# A1.net
KiCad netlist of a schematic drawn in Altium Designer
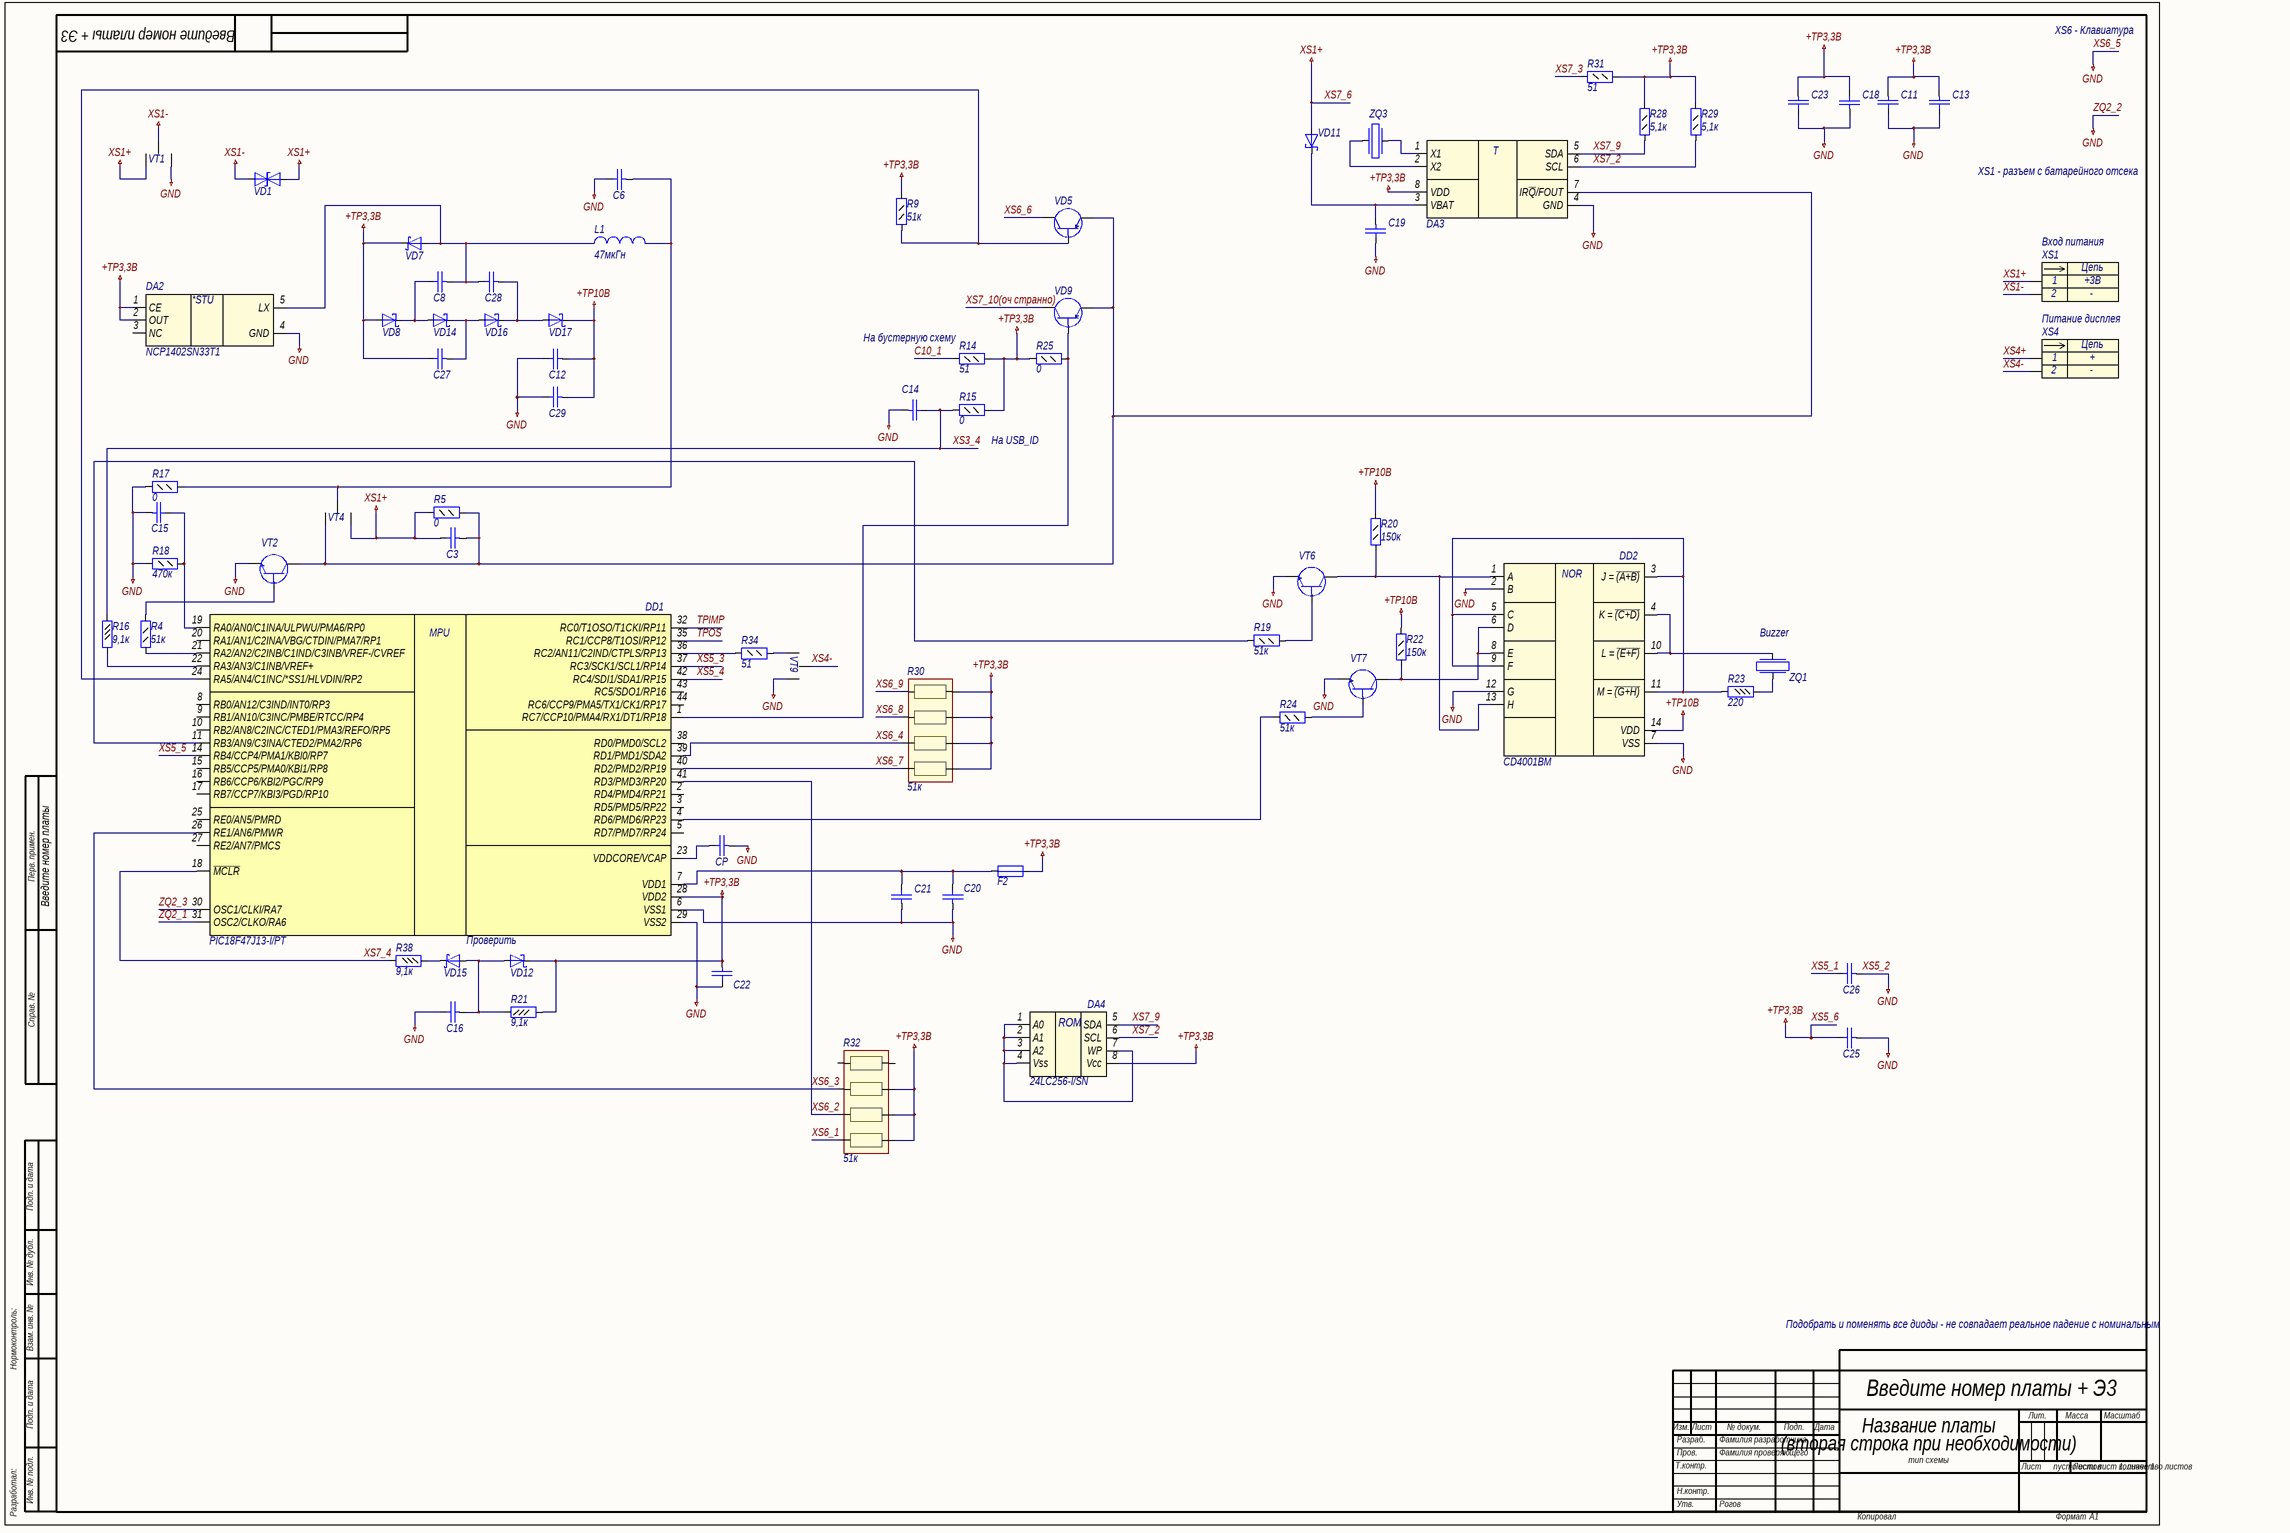
[diagram p0: A1.SchDoc]

(export (version "E")
  (design (tool "Eeschema 10.0.6"))
  (components
    (comp (ref "C3")
      (value "Capacitor")
      (footprint "C0402")
      (description "Конденсатор")
      (fields (field (name "VOLTAGE") "50B") (field (name "PART NUMBER") "GRP1555C1HR47CZ01E"))
      (libsource (lib "MOP44") (part "Capacitor"))
    )
    (comp (ref "C6")
      (value "Capacitor")
      (footprint "C0402")
      (description "Конденсатор")
      (fields (field (name "VOLTAGE") "50B") (field (name "PART NUMBER") "GRP1555C1HR47CZ01E"))
      (libsource (lib "MOP44") (part "Capacitor"))
    )
    (comp (ref "C8")
      (value "Capacitor")
      (footprint "C0402")
      (description "Конденсатор")
      (fields (field (name "VOLTAGE") "50B") (field (name "PART NUMBER") "GRP1555C1HR47CZ01E"))
      (libsource (lib "MOP44") (part "Capacitor"))
    )
    (comp (ref "C11")
      (value "Capacitor")
      (footprint "C0402")
      (description "Конденсатор")
      (fields (field (name "VOLTAGE") "50B") (field (name "PART NUMBER") "GRP1555C1HR47CZ01E"))
      (libsource (lib "MOP44") (part "Capacitor"))
    )
    (comp (ref "C12")
      (value "Capacitor")
      (footprint "C0402")
      (description "Конденсатор")
      (fields (field (name "VOLTAGE") "50B") (field (name "PART NUMBER") "GRP1555C1HR47CZ01E"))
      (libsource (lib "MOP44") (part "Capacitor"))
    )
    (comp (ref "C13")
      (value "Capacitor")
      (footprint "C0402")
      (description "Конденсатор")
      (fields (field (name "VOLTAGE") "50B") (field (name "PART NUMBER") "GRP1555C1HR47CZ01E"))
      (libsource (lib "MOP44") (part "Capacitor"))
    )
    (comp (ref "C14")
      (value "Capacitor")
      (footprint "C0402")
      (description "Конденсатор")
      (fields (field (name "VOLTAGE") "50B") (field (name "PART NUMBER") "GRP1555C1HR47CZ01E"))
      (libsource (lib "MOP44") (part "Capacitor"))
    )
    (comp (ref "C15")
      (value "Capacitor")
      (footprint "C0402")
      (description "Конденсатор")
      (fields (field (name "VOLTAGE") "50B") (field (name "PART NUMBER") "GRP1555C1HR47CZ01E"))
      (libsource (lib "MOP44") (part "Capacitor"))
    )
    (comp (ref "C16")
      (value "Capacitor")
      (footprint "C0402")
      (description "Конденсатор")
      (fields (field (name "VOLTAGE") "50B") (field (name "PART NUMBER") "GRP1555C1HR47CZ01E"))
      (libsource (lib "MOP44") (part "Capacitor"))
    )
    (comp (ref "C18")
      (value "Capacitor")
      (footprint "C0402")
      (description "Конденсатор")
      (fields (field (name "VOLTAGE") "50B") (field (name "PART NUMBER") "GRP1555C1HR47CZ01E"))
      (libsource (lib "MOP44") (part "Capacitor"))
    )
    (comp (ref "C19")
      (value "Capacitor")
      (footprint "C0402")
      (description "Конденсатор")
      (fields (field (name "VOLTAGE") "50B") (field (name "PART NUMBER") "GRP1555C1HR47CZ01E"))
      (libsource (lib "MOP44") (part "Capacitor"))
    )
    (comp (ref "C20")
      (value "Capacitor")
      (footprint "C0402")
      (description "Конденсатор")
      (fields (field (name "VOLTAGE") "50B") (field (name "PART NUMBER") "GRP1555C1HR47CZ01E"))
      (libsource (lib "MOP44") (part "Capacitor"))
    )
    (comp (ref "C21")
      (value "Capacitor")
      (footprint "C0402")
      (description "Конденсатор")
      (fields (field (name "VOLTAGE") "50B") (field (name "PART NUMBER") "GRP1555C1HR47CZ01E"))
      (libsource (lib "MOP44") (part "Capacitor"))
    )
    (comp (ref "C22")
      (value "Capacitor")
      (footprint "C0402")
      (description "Конденсатор")
      (fields (field (name "VOLTAGE") "50B") (field (name "PART NUMBER") "GRP1555C1HR47CZ01E"))
      (libsource (lib "MOP44") (part "Capacitor"))
    )
    (comp (ref "C23")
      (value "Capacitor")
      (footprint "C0402")
      (description "Конденсатор")
      (fields (field (name "VOLTAGE") "50B") (field (name "PART NUMBER") "GRP1555C1HR47CZ01E"))
      (libsource (lib "MOP44") (part "Capacitor"))
    )
    (comp (ref "C25")
      (value "Capacitor")
      (footprint "C0402")
      (description "Конденсатор")
      (fields (field (name "VOLTAGE") "50B") (field (name "PART NUMBER") "GRP1555C1HR47CZ01E"))
      (libsource (lib "MOP44") (part "Capacitor"))
    )
    (comp (ref "C26")
      (value "Capacitor")
      (footprint "C0402")
      (description "Конденсатор")
      (fields (field (name "VOLTAGE") "50B") (field (name "PART NUMBER") "GRP1555C1HR47CZ01E"))
      (libsource (lib "MOP44") (part "Capacitor"))
    )
    (comp (ref "C27")
      (value "Capacitor")
      (footprint "C0402")
      (description "Конденсатор")
      (fields (field (name "VOLTAGE") "50B") (field (name "PART NUMBER") "GRP1555C1HR47CZ01E"))
      (libsource (lib "MOP44") (part "Capacitor"))
    )
    (comp (ref "C28")
      (value "Capacitor")
      (footprint "C0402")
      (description "Конденсатор")
      (fields (field (name "VOLTAGE") "50B") (field (name "PART NUMBER") "GRP1555C1HR47CZ01E"))
      (libsource (lib "MOP44") (part "Capacitor"))
    )
    (comp (ref "C29")
      (value "Capacitor")
      (footprint "C0402")
      (description "Конденсатор")
      (fields (field (name "VOLTAGE") "50B") (field (name "PART NUMBER") "GRP1555C1HR47CZ01E"))
      (libsource (lib "MOP44") (part "Capacitor"))
    )
    (comp (ref "CP")
      (value "Capacitor")
      (footprint "C0402")
      (description "Конденсатор")
      (fields (field (name "VOLTAGE") "50B") (field (name "PART NUMBER") "GRP1555C1HR47CZ01E"))
      (libsource (lib "MOP44") (part "Capacitor"))
    )
    (comp (ref "DA2")
      (value "NCP1402")
      (footprint "SOT23-5")
      (description "Step-up DC-DC Converter for 2-V to 3.3-V")
      (fields (field (name "PART NUMBER") "NCP1402SN33T1") (field (name "MANUFACTURER") "ON Semiconductor"))
      (libsource (lib "MOP44") (part "NCP1402"))
    )
    (comp (ref "DA3")
      (value "ISL1208IB8Z")
      (footprint "SO8")
      (description "Часы реального времени/календарь")
      (libsource (lib "MOP44") (part "ISL1208IB8Z"))
    )
    (comp (ref "DA4")
      (value "24LC256-I/SN")
      (footprint "SO8")
      (description "Последовательная энергонезависимая память 32x8kbit")
      (fields (field (name "PART NUMBER") "24LC256-I/SN") (field (name "MANUFACTURER") "Microchip"))
      (libsource (lib "MOP44") (part "24LC256-I/SN"))
    )
    (comp (ref "DD1")
      (value "PIC18F47J13-I/PT")
      (footprint "TQFP-44")
      (description "Микроконтроллер 8-Бит, 44-pin")
      (libsource (lib "MOP44") (part "PIC18F47J13-I/PT"))
    )
    (comp (ref "DD2")
      (value "CD4001BM")
      (footprint "SO14")
      (description "CMOS NOR Gate 4-Element 2-IN")
      (libsource (lib "MOP44") (part "CD4001BM"))
    )
    (comp (ref "F2")
      (value "Fuse")
      (footprint "FUSE812")
      (description "Предохранитель")
      (fields (field (name "PART NUMBER") "MF-MSMF075"))
      (libsource (lib "MOP44") (part "Fuse"))
    )
    (comp (ref "L1")
      (value "47мкГн")
      (footprint "SDR0604")
      (description "EMI Suppression Filter")
      (fields (field (name "PART NUMBER") "SDR0604- 470KL") (field (name "Comment") "Inductor"))
      (libsource (lib "MOP44") (part "Inductor"))
    )
    (comp (ref "R4")
      (value "51к")
      (footprint "R0805")
      (description "Резистор")
      (fields (field (name "PART NUMBER") "RC0805FR-0751KL") (field (name "POWER") "0,125Вт"))
      (libsource (lib "MOP44") (part "Resistor_0,125Вт"))
    )
    (comp (ref "R5")
      (value "0")
      (footprint "R0805")
      (description "Резистор")
      (fields (field (name "PART NUMBER") "RC0805FR-070RL") (field (name "POWER") "0,125Вт"))
      (libsource (lib "") (part "Resistor_0,125Вт_1"))
    )
    (comp (ref "R9")
      (value "51к")
      (footprint "R0805")
      (description "Резистор")
      (fields (field (name "PART NUMBER") "RC0805FR-0751KL") (field (name "POWER") "0,125Вт"))
      (libsource (lib "MOP44") (part "Resistor_0,125Вт"))
    )
    (comp (ref "R14")
      (value "51")
      (footprint "R0805")
      (description "Резистор")
      (fields (field (name "PART NUMBER") "RC0805FR-0751RL") (field (name "POWER") "0,125Вт"))
      (libsource (lib "") (part "Resistor_0,125Вт_1"))
    )
    (comp (ref "R15")
      (value "0")
      (footprint "R0805")
      (description "Резистор")
      (fields (field (name "PART NUMBER") "RC0805FR-070RL") (field (name "POWER") "0,125Вт"))
      (libsource (lib "") (part "Resistor_0,125Вт_1"))
    )
    (comp (ref "R16")
      (value "9,1к")
      (footprint "R0603")
      (description "Резистор")
      (fields (field (name "PART NUMBER") "RC0603FR-079K1") (field (name "POWER") "0,062Вт"))
      (libsource (lib "") (part "Resistor_0,062Вт_2"))
    )
    (comp (ref "R17")
      (value "0")
      (footprint "R0805")
      (description "Резистор")
      (fields (field (name "PART NUMBER") "RC0805FR-070RL") (field (name "POWER") "0,125Вт"))
      (libsource (lib "") (part "Resistor_0,125Вт_1"))
    )
    (comp (ref "R18")
      (value "470к")
      (footprint "R0805")
      (description "Резистор")
      (fields (field (name "PART NUMBER") "RC0805FR-07470KL") (field (name "POWER") "0,125Вт"))
      (libsource (lib "") (part "Resistor_0,125Вт_2"))
    )
    (comp (ref "R19")
      (value "51к")
      (footprint "R0805")
      (description "Резистор")
      (fields (field (name "PART NUMBER") "RC0805FR-0751KL") (field (name "POWER") "0,125Вт"))
      (libsource (lib "") (part "Resistor_0,125Вт_1"))
    )
    (comp (ref "R20")
      (value "150к")
      (footprint "R0805")
      (description "Резистор")
      (fields (field (name "PART NUMBER") "RC0805FR-07150KL") (field (name "POWER") "0,125Вт"))
      (libsource (lib "MOP44") (part "Resistor_0,125Вт"))
    )
    (comp (ref "R21")
      (value "9,1к")
      (footprint "R0603")
      (description "Резистор")
      (fields (field (name "PART NUMBER") "RC0603FR-079K1") (field (name "POWER") "0,062Вт"))
      (libsource (lib "") (part "Resistor_0,062Вт_1"))
    )
    (comp (ref "R22")
      (value "150к")
      (footprint "R0805")
      (description "Резистор")
      (fields (field (name "PART NUMBER") "RC0805FR-07150KL") (field (name "POWER") "0,125Вт"))
      (libsource (lib "MOP44") (part "Resistor_0,125Вт"))
    )
    (comp (ref "R23")
      (value "220")
      (footprint "R0603")
      (description "Резистор")
      (fields (field (name "PART NUMBER") "RC0603FR-07220RL") (field (name "POWER") "0,062Вт"))
      (libsource (lib "MOP44") (part "Resistor_0,062Вт"))
    )
    (comp (ref "R24")
      (value "51к")
      (footprint "R0805")
      (description "Резистор")
      (fields (field (name "PART NUMBER") "RC0805FR-0751KL") (field (name "POWER") "0,125Вт"))
      (libsource (lib "") (part "Resistor_0,125Вт_1"))
    )
    (comp (ref "R25")
      (value "0")
      (footprint "R0805")
      (description "Резистор")
      (fields (field (name "PART NUMBER") "RC0805FR-070RL") (field (name "POWER") "0,125Вт"))
      (libsource (lib "") (part "Resistor_0,125Вт_1"))
    )
    (comp (ref "R28")
      (value "5,1к")
      (footprint "R0805")
      (description "Резистор")
      (fields (field (name "PART NUMBER") "RC0805FR-075K1") (field (name "POWER") "0,125Вт"))
      (libsource (lib "MOP44") (part "Resistor_0,125Вт"))
    )
    (comp (ref "R29")
      (value "5,1к")
      (footprint "R0805")
      (description "Резистор")
      (fields (field (name "PART NUMBER") "RC0805FR-075K1") (field (name "POWER") "0,125Вт"))
      (libsource (lib "MOP44") (part "Resistor_0,125Вт"))
    )
    (comp (ref "R30")
      (value "51к")
      (footprint "4xR1206")
      (description "Резисторная сборка")
      (fields (field (name "PART NUMBER") "TC164-JR-0751KL") (field (name "POWER") "0,062Вт"))
      (libsource (lib "MOP44") (part "Resistors_array_4x0,062Вт"))
    )
    (comp (ref "R31")
      (value "51")
      (footprint "R0805")
      (description "Резистор")
      (fields (field (name "PART NUMBER") "RC0805FR-0751RL") (field (name "POWER") "0,125Вт"))
      (libsource (lib "") (part "Resistor_0,125Вт_2"))
    )
    (comp (ref "R32")
      (value "51к")
      (footprint "4xR1206")
      (description "Резисторная сборка")
      (fields (field (name "PART NUMBER") "TC164-JR-0751KL") (field (name "POWER") "0,062Вт"))
      (libsource (lib "MOP44") (part "Resistors_array_4x0,062Вт"))
    )
    (comp (ref "R34")
      (value "51")
      (footprint "R0805")
      (description "Резистор")
      (fields (field (name "PART NUMBER") "RC0805FR-0751RL") (field (name "POWER") "0,125Вт"))
      (libsource (lib "") (part "Resistor_0,125Вт_2"))
    )
    (comp (ref "R38")
      (value "9,1к")
      (footprint "R0603")
      (description "Резистор")
      (fields (field (name "PART NUMBER") "RC0603FR-079K1") (field (name "POWER") "0,062Вт"))
      (libsource (lib "MOP44") (part "Resistor_0,062Вт"))
    )
    (comp (ref "VD1")
      (value "DiodeZenerDual")
      (footprint "SMB")
      (description "Cтабилитрон (диод выпрямительный лавинный) двусторонний")
      (fields (field (name "PART NUMBER") "SMBJ8.5CA"))
      (libsource (lib "MOP44") (part "DiodeZenerDual"))
    )
    (comp (ref "VD5")
      (value "BJT PNP")
      (footprint "SOT23-3")
      (fields (field (name "POWER") "0,31Вт") (field (name "PART NUMBER") "BC807-40"))
      (libsource (lib "MOP44") (part "BJT PNP"))
    )
    (comp (ref "VD7")
      (value "DiodeSchottky")
      (footprint "SOD-123")
      (description "Диод Шоттки")
      (fields (field (name "PART NUMBER") "MBR0520LT1"))
      (libsource (lib "MOP44") (part "DiodeSchottky"))
    )
    (comp (ref "VD8")
      (value "DiodeSchottky")
      (footprint "SOD-123")
      (description "Диод Шоттки")
      (fields (field (name "PART NUMBER") "MBR0520LT1"))
      (libsource (lib "MOP44") (part "DiodeSchottky"))
    )
    (comp (ref "VD9")
      (value "BJT PNP")
      (footprint "SOT23-3")
      (fields (field (name "POWER") "0,31Вт") (field (name "PART NUMBER") "BC807-40"))
      (libsource (lib "MOP44") (part "BJT PNP"))
    )
    (comp (ref "VD11")
      (value "DiodeSchottky")
      (footprint "SOD-123")
      (description "Диод Шоттки")
      (fields (field (name "PART NUMBER") "MBR0540"))
      (libsource (lib "MOP44") (part "DiodeSchottky"))
    )
    (comp (ref "VD12")
      (value "DiodeSchottky")
      (footprint "SOD-123")
      (description "Диод Шоттки")
      (fields (field (name "PART NUMBER") "MBR0520LT1"))
      (libsource (lib "MOP44") (part "DiodeSchottky"))
    )
    (comp (ref "VD14")
      (value "DiodeSchottky")
      (footprint "SOD-123")
      (description "Диод Шоттки")
      (fields (field (name "PART NUMBER") "MBR0520LT1"))
      (libsource (lib "MOP44") (part "DiodeSchottky"))
    )
    (comp (ref "VD15")
      (value "DiodeSchottky")
      (footprint "SOD-123")
      (description "Диод Шоттки")
      (fields (field (name "PART NUMBER") "MBR0520LT1"))
      (libsource (lib "MOP44") (part "DiodeSchottky"))
    )
    (comp (ref "VD16")
      (value "DiodeSchottky")
      (footprint "SOD-123")
      (description "Диод Шоттки")
      (fields (field (name "PART NUMBER") "MBR0520LT1"))
      (libsource (lib "MOP44") (part "DiodeSchottky"))
    )
    (comp (ref "VD17")
      (value "DiodeSchottky")
      (footprint "SOD-123")
      (description "Диод Шоттки")
      (fields (field (name "PART NUMBER") "MBR0520LT1"))
      (libsource (lib "MOP44") (part "DiodeSchottky"))
    )
    (comp (ref "VT2")
      (value "BJT NPN")
      (footprint "SOT23-3")
      (fields (field (name "POWER") "0,25Bт") (field (name "PART NUMBER") "BC847C"))
      (libsource (lib "MOP44") (part "BJT NPN"))
    )
    (comp (ref "VT6")
      (value "BJT NPN")
      (footprint "SOT23-3")
      (fields (field (name "POWER") "0,25Bт") (field (name "PART NUMBER") "BC847C"))
      (libsource (lib "MOP44") (part "BJT NPN"))
    )
    (comp (ref "VT7")
      (value "BJT NPN")
      (footprint "SOT23-3")
      (fields (field (name "POWER") "0,25Bт") (field (name "PART NUMBER") "BC847C"))
      (libsource (lib "MOP44") (part "BJT NPN"))
    )
    (comp (ref "XS1")
      (value "Вход питания")
      (footprint "CWF-2")
      (description "Разъем - 2 конт. вилка")
      (fields (field (name "PART NUMBER") "DS1069-2MVW6X"))
      (libsource (lib "MOP44") (part "Header_2_plg"))
    )
    (comp (ref "XS4")
      (value "Питание дисплея")
      (footprint "CWF-2")
      (description "Разъем - 2 конт. вилка")
      (fields (field (name "PART NUMBER") "DS1069-2MVW6X"))
      (libsource (lib "MOP44") (part "Header_2_plg"))
    )
    (comp (ref "ZQ1")
      (value "~")
      (footprint "Buzzer_9mm")
      (description "Пьезоизлучатель звуковой без генератора")
      (fields (field (name "PART NUMBER") "HC0905F"))
      (libsource (lib "MOP44") (part "Buzzer"))
    )
    (comp (ref "ZQ3")
      (value "Crystal")
      (footprint "QSMD7x1.5x1.4")
      (description "Кварцевый резонатор")
      (fields (field (name "PART NUMBER") "KX-327LT"))
      (libsource (lib "MOP44") (part "Crystal"))
    )
  )
  (nets
    (net (code "1") (name "+TP3,3В") (class "Default")
      (node (ref "C11") (pin "1") (pinfunction "1_1") (pintype "passive"))
      (node (ref "C13") (pin "1") (pinfunction "1_1") (pintype "passive"))
      (node (ref "C18") (pin "2") (pinfunction "2_2") (pintype "passive"))
      (node (ref "C22") (pin "1") (pinfunction "1_1") (pintype "passive"))
      (node (ref "C23") (pin "1") (pinfunction "1_1") (pintype "passive"))
      (node (ref "C25") (pin "2") (pinfunction "2_2") (pintype "passive"))
      (node (ref "C27") (pin "2") (pinfunction "2_2") (pintype "passive"))
      (node (ref "DA2") (pin "1") (pinfunction "CE_1") (pintype "power_in"))
      (node (ref "DA2") (pin "2") (pinfunction "OUT_2") (pintype "power_in"))
      (node (ref "DA3") (pin "8") (pinfunction "VDD_8") (pintype "power_in"))
      (node (ref "DA4") (pin "8") (pinfunction "Vcc_8") (pintype "passive"))
      (node (ref "DD1") (pin "28") (pinfunction "VDD2_28") (pintype "passive"))
      (node (ref "F2") (pin "2") (pinfunction "2_2") (pintype "passive"))
      (node (ref "R14") (pin "2") (pinfunction "2_2") (pintype "passive"))
      (node (ref "R15") (pin "2") (pinfunction "2_2") (pintype "passive"))
      (node (ref "R21") (pin "2") (pinfunction "2_2") (pintype "passive"))
      (node (ref "R25") (pin "1") (pinfunction "1_1") (pintype "passive"))
      (node (ref "R28") (pin "2") (pinfunction "2_2") (pintype "passive"))
      (node (ref "R29") (pin "2") (pinfunction "2_2") (pintype "passive"))
      (node (ref "R30") (pin "2") (pinfunction "2_2") (pintype "passive"))
      (node (ref "R30") (pin "4") (pinfunction "4_4") (pintype "passive"))
      (node (ref "R30") (pin "6") (pinfunction "6_6") (pintype "passive"))
      (node (ref "R30") (pin "8") (pinfunction "8_8") (pintype "passive"))
      (node (ref "R31") (pin "1") (pinfunction "1_1") (pintype "passive"))
      (node (ref "R32") (pin "4") (pinfunction "4_4") (pintype "passive"))
      (node (ref "R32") (pin "6") (pinfunction "6_6") (pintype "passive"))
      (node (ref "R32") (pin "8") (pinfunction "8_8") (pintype "passive"))
      (node (ref "R9") (pin "2") (pinfunction "2_2") (pintype "passive"))
      (node (ref "VD12") (pin "1") (pinfunction "K_1") (pintype "passive"))
      (node (ref "VD7") (pin "1") (pinfunction "K_1") (pintype "passive"))
      (node (ref "VD8") (pin "2") (pinfunction "A_2") (pintype "passive"))
    )
    (net (code "2") (name "+TP10В") (class "Default")
      (node (ref "C12") (pin "1") (pinfunction "1_1") (pintype "passive"))
      (node (ref "C29") (pin "1") (pinfunction "1_1") (pintype "passive"))
      (node (ref "DD2") (pin "14") (pinfunction "VDD_14") (pintype "power_in"))
      (node (ref "R20") (pin "2") (pinfunction "2_2") (pintype "passive"))
      (node (ref "R22") (pin "2") (pinfunction "2_2") (pintype "passive"))
      (node (ref "VD17") (pin "1") (pinfunction "K_1") (pintype "passive"))
    )
    (net (code "3") (name "/C10_1") (class "Default")
      (node (ref "R14") (pin "1") (pinfunction "1_1") (pintype "passive"))
    )
    (net (code "4") (name "/TPIMP") (class "Default")
      (node (ref "DD1") (pin "32") (pinfunction "RC0/T1OSO/T1CKI/RP11_32") (pintype "passive"))
    )
    (net (code "5") (name "/TPOS") (class "Default")
      (node (ref "DD1") (pin "35") (pinfunction "RC1/CCP8/T1OSI/RP12_35") (pintype "passive"))
    )
    (net (code "6") (name "/XS3_4") (class "Default")
      (node (ref "C14") (pin "2") (pinfunction "2_2") (pintype "passive"))
      (node (ref "R15") (pin "1") (pinfunction "1_1") (pintype "passive"))
      (node (ref "R16") (pin "1") (pinfunction "1_1") (pintype "passive"))
    )
    (net (code "7") (name "/XS4+") (class "Default")
      (node (ref "XS4") (pin "1") (pinfunction "1_1") (pintype "passive"))
    )
    (net (code "8") (name "/XS4-") (class "Default")
      (node (ref "XS4") (pin "2") (pinfunction "2_2") (pintype "passive"))
    )
    (net (code "9") (name "/XS5_1") (class "Default")
      (node (ref "C26") (pin "2") (pinfunction "2_2") (pintype "passive"))
    )
    (net (code "10") (name "/XS5_3") (class "Default")
      (node (ref "DD1") (pin "37") (pinfunction "RC3/SCK1/SCL1/RP14_37") (pintype "passive"))
    )
    (net (code "11") (name "/XS5_4") (class "Default")
      (node (ref "DD1") (pin "42") (pinfunction "RC4/SDI1/SDA1/RP15_42") (pintype "passive"))
    )
    (net (code "12") (name "/XS5_5") (class "Default")
      (node (ref "DD1") (pin "14") (pinfunction "RB4/CCP4/PMA1/KBI0/RP7_14") (pintype "passive"))
    )
    (net (code "13") (name "/XS6_1") (class "Default")
      (node (ref "R32") (pin "7") (pinfunction "7_7") (pintype "passive"))
    )
    (net (code "14") (name "/XS6_2") (class "Default")
      (node (ref "DD1") (pin "26") (pinfunction "RE1/AN6/PMWR_26") (pintype "passive"))
      (node (ref "DD1") (pin "41") (pinfunction "RD3/PMD3/RP20_41") (pintype "passive"))
      (node (ref "R32") (pin "3") (pinfunction "3_3") (pintype "passive"))
      (node (ref "R32") (pin "5") (pinfunction "5_5") (pintype "passive"))
    )
    (net (code "15") (name "/XS6_4") (class "Default")
      (node (ref "DD1") (pin "39") (pinfunction "RD1/PMD1/SDA2_39") (pintype "passive"))
      (node (ref "R30") (pin "5") (pinfunction "5_5") (pintype "passive"))
    )
    (net (code "16") (name "/XS6_6") (class "Default")
      (node (ref "VD5") (pin "3") (pinfunction "3_3") (pintype "passive"))
    )
    (net (code "17") (name "/XS6_7") (class "Default")
      (node (ref "DD1") (pin "40") (pinfunction "RD2/PMD2/RP19_40") (pintype "passive"))
      (node (ref "R30") (pin "7") (pinfunction "7_7") (pintype "passive"))
    )
    (net (code "18") (name "/XS6_8") (class "Default")
      (node (ref "R30") (pin "3") (pinfunction "3_3") (pintype "passive"))
    )
    (net (code "19") (name "/XS6_9") (class "Default")
      (node (ref "R30") (pin "1") (pinfunction "1_1") (pintype "passive"))
    )
    (net (code "20") (name "/XS7_2") (class "Default")
      (node (ref "DA3") (pin "6") (pinfunction "SCL_6") (pintype "power_in"))
      (node (ref "DA4") (pin "6") (pinfunction "SCL_6") (pintype "passive"))
      (node (ref "R29") (pin "1") (pinfunction "1_1") (pintype "passive"))
    )
    (net (code "21") (name "/XS7_3") (class "Default")
      (node (ref "R31") (pin "2") (pinfunction "2_2") (pintype "passive"))
    )
    (net (code "22") (name "/XS7_4") (class "Default")
      (node (ref "DD1") (pin "18") (pinfunction "~{MCLR}_18") (pintype "passive"))
      (node (ref "R38") (pin "2") (pinfunction "2_2") (pintype "passive"))
    )
    (net (code "23") (name "/XS7_9") (class "Default")
      (node (ref "DA3") (pin "5") (pinfunction "SDA_5") (pintype "power_in"))
      (node (ref "DA4") (pin "5") (pinfunction "SDA_5") (pintype "passive"))
      (node (ref "R28") (pin "1") (pinfunction "1_1") (pintype "passive"))
    )
    (net (code "24") (name "/XS7_10(оч странно)") (class "Default")
      (node (ref "VD9") (pin "3") (pinfunction "3_3") (pintype "passive"))
    )
    (net (code "25") (name "/ZQ2_1") (class "Default")
      (node (ref "DD1") (pin "31") (pinfunction "OSC2/CLKO/RA6_31") (pintype "passive"))
    )
    (net (code "26") (name "/ZQ2_3") (class "Default")
      (node (ref "DD1") (pin "30") (pinfunction "OSC1/CLKI/RA7_30") (pintype "passive"))
    )
    (net (code "27") (name "GND") (class "Default")
      (node (ref "C11") (pin "2") (pinfunction "2_2") (pintype "passive"))
      (node (ref "C12") (pin "2") (pinfunction "2_2") (pintype "passive"))
      (node (ref "C13") (pin "2") (pinfunction "2_2") (pintype "passive"))
      (node (ref "C14") (pin "1") (pinfunction "1_1") (pintype "passive"))
      (node (ref "C15") (pin "1") (pinfunction "1_1") (pintype "passive"))
      (node (ref "C16") (pin "2") (pinfunction "2_2") (pintype "passive"))
      (node (ref "C18") (pin "1") (pinfunction "1_1") (pintype "passive"))
      (node (ref "C19") (pin "2") (pinfunction "2_2") (pintype "passive"))
      (node (ref "C20") (pin "1") (pinfunction "1_1") (pintype "passive"))
      (node (ref "C21") (pin "1") (pinfunction "1_1") (pintype "passive"))
      (node (ref "C22") (pin "2") (pinfunction "2_2") (pintype "passive"))
      (node (ref "C23") (pin "2") (pinfunction "2_2") (pintype "passive"))
      (node (ref "C25") (pin "1") (pinfunction "1_1") (pintype "passive"))
      (node (ref "C26") (pin "1") (pinfunction "1_1") (pintype "passive"))
      (node (ref "C29") (pin "2") (pinfunction "2_2") (pintype "passive"))
      (node (ref "C6") (pin "2") (pinfunction "2_2") (pintype "passive"))
      (node (ref "CP") (pin "1") (pinfunction "1_1") (pintype "passive"))
      (node (ref "DA2") (pin "4") (pinfunction "GND_4") (pintype "power_in"))
      (node (ref "DA3") (pin "4") (pinfunction "GND_4") (pintype "power_in"))
      (node (ref "DD1") (pin "29") (pinfunction "VSS2_29") (pintype "passive"))
      (node (ref "DD1") (pin "6") (pinfunction "VSS1_6") (pintype "passive"))
      (node (ref "DD2") (pin "12") (pinfunction "G_12") (pintype "passive"))
      (node (ref "DD2") (pin "2") (pinfunction "B_2") (pintype "passive"))
      (node (ref "DD2") (pin "7") (pinfunction "VSS_7") (pintype "power_in"))
      (node (ref "R17") (pin "1") (pinfunction "1_1") (pintype "passive"))
      (node (ref "R18") (pin "2") (pinfunction "2_2") (pintype "passive"))
      (node (ref "VT2") (pin "2") (pinfunction "2_2") (pintype "passive"))
      (node (ref "VT6") (pin "2") (pinfunction "2_2") (pintype "passive"))
      (node (ref "VT7") (pin "2") (pinfunction "2_2") (pintype "passive"))
    )
    (net (code "28") (name "Net-(C6-Pad1)") (class "Default")
      (node (ref "C6") (pin "1") (pinfunction "1_1") (pintype "passive"))
      (node (ref "L1") (pin "2") (pinfunction "2_2") (pintype "passive"))
      (node (ref "R17") (pin "2") (pinfunction "2_2") (pintype "passive"))
    )
    (net (code "29") (name "Net-(DA2-LX)") (class "Default")
      (node (ref "C28") (pin "2") (pinfunction "2_2") (pintype "passive"))
      (node (ref "C8") (pin "1") (pinfunction "1_1") (pintype "passive"))
      (node (ref "DA2") (pin "5") (pinfunction "LX_5") (pintype "power_in"))
      (node (ref "L1") (pin "1") (pinfunction "1_1") (pintype "passive"))
      (node (ref "VD7") (pin "2") (pinfunction "A_2") (pintype "passive"))
    )
    (net (code "30") (name "Net-(DA3-IR~{Q}{slash}FOUT)") (class "Default")
      (node (ref "C3") (pin "1") (pinfunction "1_1") (pintype "passive"))
      (node (ref "DA3") (pin "7") (pinfunction "IR~{Q}/FOUT_7") (pintype "power_in"))
      (node (ref "R5") (pin "2") (pinfunction "2_2") (pintype "passive"))
      (node (ref "VD5") (pin "2") (pinfunction "2_2") (pintype "passive"))
      (node (ref "VD9") (pin "2") (pinfunction "2_2") (pintype "passive"))
      (node (ref "VT2") (pin "3") (pinfunction "3_3") (pintype "passive"))
    )
    (net (code "31") (name "Net-(DA3-VBAT)") (class "Default")
      (node (ref "C19") (pin "1") (pinfunction "1_1") (pintype "passive"))
      (node (ref "DA3") (pin "3") (pinfunction "VBAT_3") (pintype "power_in"))
      (node (ref "VD11") (pin "1") (pinfunction "K_1") (pintype "passive"))
    )
    (net (code "32") (name "Net-(DA3-X1)") (class "Default")
      (node (ref "DA3") (pin "1") (pinfunction "X1_1") (pintype "power_in"))
      (node (ref "ZQ3") (pin "2") (pinfunction "2_2") (pintype "passive"))
    )
    (net (code "33") (name "Net-(DA3-X2)") (class "Default")
      (node (ref "DA3") (pin "2") (pinfunction "X2_2") (pintype "power_in"))
      (node (ref "ZQ3") (pin "1") (pinfunction "1_1") (pintype "passive"))
    )
    (net (code "34") (name "Net-(DA4-A0)") (class "Default")
      (node (ref "DA4") (pin "1") (pinfunction "A0_1") (pintype "passive"))
      (node (ref "DA4") (pin "2") (pinfunction "A1_2") (pintype "passive"))
      (node (ref "DA4") (pin "3") (pinfunction "A2_3") (pintype "passive"))
      (node (ref "DA4") (pin "4") (pinfunction "Vss_4") (pintype "passive"))
      (node (ref "DA4") (pin "7") (pinfunction "WP_7") (pintype "passive"))
    )
    (net (code "35") (name "Net-(DD1-RA0{slash}AN0{slash}C1INA{slash}ULPWU{slash}PMA6{slash}RP0)") (class "Default")
      (node (ref "C15") (pin "2") (pinfunction "2_2") (pintype "passive"))
      (node (ref "DD1") (pin "19") (pinfunction "RA0/AN0/C1INA/ULPWU/PMA6/RP0_19") (pintype "passive"))
      (node (ref "R18") (pin "1") (pinfunction "1_1") (pintype "passive"))
    )
    (net (code "36") (name "Net-(DD1-RA2{slash}AN2{slash}C2INB{slash}C1IND{slash}C3INB{slash}VREF-{slash}CVREF)") (class "Default")
      (node (ref "DD1") (pin "21") (pinfunction "RA2/AN2/C2INB/C1IND/C3INB/VREF-/CVREF_21") (pintype "passive"))
      (node (ref "R4") (pin "1") (pinfunction "1_1") (pintype "passive"))
    )
    (net (code "37") (name "Net-(DD1-RA3{slash}AN3{slash}C1INB{slash}VREF+)") (class "Default")
      (node (ref "DD1") (pin "22") (pinfunction "RA3/AN3/C1INB/VREF+_22") (pintype "passive"))
      (node (ref "R16") (pin "2") (pinfunction "2_2") (pintype "passive"))
    )
    (net (code "38") (name "Net-(DD1-RA5{slash}AN4{slash}C1INC{slash}*SS1{slash}HLVDIN{slash}RP2)") (class "Default")
      (node (ref "DD1") (pin "24") (pinfunction "RA5/AN4/C1INC/*SS1/HLVDIN/RP2_24") (pintype "passive"))
      (node (ref "R9") (pin "1") (pinfunction "1_1") (pintype "passive"))
      (node (ref "VD5") (pin "1") (pinfunction "1_1") (pintype "passive"))
    )
    (net (code "39") (name "Net-(DD1-RB3{slash}AN9{slash}C3INA{slash}CTED2{slash}PMA2{slash}RP6)") (class "Default")
      (node (ref "DD1") (pin "11") (pinfunction "RB3/AN9/C3INA/CTED2/PMA2/RP6_11") (pintype "passive"))
      (node (ref "R19") (pin "1") (pinfunction "1_1") (pintype "passive"))
    )
    (net (code "40") (name "Net-(DD1-RC2{slash}AN11{slash}C2IND{slash}CTPLS{slash}RP13)") (class "Default")
      (node (ref "DD1") (pin "36") (pinfunction "RC2/AN11/C2IND/CTPLS/RP13_36") (pintype "passive"))
      (node (ref "R34") (pin "2") (pinfunction "2_2") (pintype "passive"))
    )
    (net (code "41") (name "Net-(DD1-RC7{slash}CCP10{slash}PMA4{slash}RX1{slash}DT1{slash}RP18)") (class "Default")
      (node (ref "DD1") (pin "1") (pinfunction "RC7/CCP10/PMA4/RX1/DT1/RP18_1") (pintype "passive"))
      (node (ref "R25") (pin "2") (pinfunction "2_2") (pintype "passive"))
      (node (ref "VD9") (pin "1") (pinfunction "1_1") (pintype "passive"))
    )
    (net (code "42") (name "Net-(DD1-RD6{slash}PMD6{slash}RP23)") (class "Default")
      (node (ref "DD1") (pin "4") (pinfunction "RD6/PMD6/RP23_4") (pintype "passive"))
      (node (ref "R24") (pin "1") (pinfunction "1_1") (pintype "passive"))
    )
    (net (code "43") (name "Net-(DD1-VDD1)") (class "Default")
      (node (ref "C20") (pin "2") (pinfunction "2_2") (pintype "passive"))
      (node (ref "C21") (pin "2") (pinfunction "2_2") (pintype "passive"))
      (node (ref "DD1") (pin "7") (pinfunction "VDD1_7") (pintype "passive"))
      (node (ref "F2") (pin "1") (pinfunction "1_1") (pintype "passive"))
    )
    (net (code "44") (name "Net-(DD1-VDDCORE{slash}VCAP)") (class "Default")
      (node (ref "CP") (pin "2") (pinfunction "2_2") (pintype "passive"))
      (node (ref "DD1") (pin "23") (pinfunction "VDDCORE/VCAP_23") (pintype "passive"))
    )
    (net (code "45") (name "Net-(DD2-A)") (class "Default")
      (node (ref "DD2") (pin "1") (pinfunction "A_1") (pintype "passive"))
      (node (ref "DD2") (pin "13") (pinfunction "H_13") (pintype "passive"))
      (node (ref "R20") (pin "1") (pinfunction "1_1") (pintype "passive"))
      (node (ref "VT6") (pin "3") (pinfunction "3_3") (pintype "passive"))
    )
    (net (code "46") (name "Net-(DD2-C)") (class "Default")
      (node (ref "DD2") (pin "11") (pinfunction "M_=_~{(G+H)}_11") (pintype "passive"))
      (node (ref "DD2") (pin "3") (pinfunction "J_=_~{(A+B)}_3") (pintype "passive"))
      (node (ref "DD2") (pin "5") (pinfunction "C_5") (pintype "passive"))
      (node (ref "DD2") (pin "9") (pinfunction "F_9") (pintype "passive"))
      (node (ref "R23") (pin "2") (pinfunction "2_2") (pintype "passive"))
    )
    (net (code "47") (name "Net-(DD2-D)") (class "Default")
      (node (ref "DD2") (pin "6") (pinfunction "D_6") (pintype "passive"))
      (node (ref "DD2") (pin "8") (pinfunction "E_8") (pintype "passive"))
      (node (ref "R22") (pin "1") (pinfunction "1_1") (pintype "passive"))
      (node (ref "VT7") (pin "3") (pinfunction "3_3") (pintype "passive"))
    )
    (net (code "48") (name "Net-(DD2-K_=_~{(C+D)})") (class "Default")
      (node (ref "DD2") (pin "10") (pinfunction "L_=_~{(E+F)}_10") (pintype "passive"))
      (node (ref "DD2") (pin "4") (pinfunction "K_=_~{(C+D)}_4") (pintype "passive"))
      (node (ref "ZQ1") (pin "2") (pinfunction "2_2") (pintype "passive"))
    )
    (net (code "49") (name "Net-(R4-Pad2)") (class "Default")
      (node (ref "R4") (pin "2") (pinfunction "2_2") (pintype "passive"))
      (node (ref "VT2") (pin "1") (pinfunction "1_1") (pintype "passive"))
    )
    (net (code "50") (name "Net-(R19-Pad2)") (class "Default")
      (node (ref "R19") (pin "2") (pinfunction "2_2") (pintype "passive"))
      (node (ref "VT6") (pin "1") (pinfunction "1_1") (pintype "passive"))
    )
    (net (code "51") (name "Net-(R23-Pad1)") (class "Default")
      (node (ref "R23") (pin "1") (pinfunction "1_1") (pintype "passive"))
      (node (ref "ZQ1") (pin "1") (pinfunction "1_1") (pintype "passive"))
    )
    (net (code "52") (name "Net-(R24-Pad2)") (class "Default")
      (node (ref "R24") (pin "2") (pinfunction "2_2") (pintype "passive"))
      (node (ref "VT7") (pin "1") (pinfunction "1_1") (pintype "passive"))
    )
    (net (code "53") (name "Net-(VD12-A)") (class "Default")
      (node (ref "C16") (pin "1") (pinfunction "1_1") (pintype "passive"))
      (node (ref "R21") (pin "1") (pinfunction "1_1") (pintype "passive"))
      (node (ref "VD12") (pin "2") (pinfunction "A_2") (pintype "passive"))
      (node (ref "VD15") (pin "2") (pinfunction "A_2") (pintype "passive"))
    )
    (net (code "54") (name "Net-(VD14-A)") (class "Default")
      (node (ref "C8") (pin "2") (pinfunction "2_2") (pintype "passive"))
      (node (ref "VD14") (pin "2") (pinfunction "A_2") (pintype "passive"))
      (node (ref "VD8") (pin "1") (pinfunction "K_1") (pintype "passive"))
    )
    (net (code "55") (name "Net-(VD14-K)") (class "Default")
      (node (ref "C27") (pin "1") (pinfunction "1_1") (pintype "passive"))
      (node (ref "VD14") (pin "1") (pinfunction "K_1") (pintype "passive"))
      (node (ref "VD16") (pin "2") (pinfunction "A_2") (pintype "passive"))
    )
    (net (code "56") (name "Net-(VD15-K)") (class "Default")
      (node (ref "R38") (pin "1") (pinfunction "1_1") (pintype "passive"))
      (node (ref "VD15") (pin "1") (pinfunction "K_1") (pintype "passive"))
    )
    (net (code "57") (name "Net-(VD16-K)") (class "Default")
      (node (ref "C28") (pin "1") (pinfunction "1_1") (pintype "passive"))
      (node (ref "VD16") (pin "1") (pinfunction "K_1") (pintype "passive"))
      (node (ref "VD17") (pin "2") (pinfunction "A_2") (pintype "passive"))
    )
    (net (code "58") (name "XS1+") (class "Default")
      (node (ref "C3") (pin "2") (pinfunction "2_2") (pintype "passive"))
      (node (ref "R5") (pin "1") (pinfunction "1_1") (pintype "passive"))
      (node (ref "VD1") (pin "1") (pinfunction "K_1") (pintype "passive"))
      (node (ref "VD11") (pin "2") (pinfunction "A_2") (pintype "passive"))
      (node (ref "XS1") (pin "1") (pinfunction "1_1") (pintype "passive"))
    )
    (net (code "59") (name "XS1-") (class "Default")
      (node (ref "VD1") (pin "2") (pinfunction "A_2") (pintype "passive"))
      (node (ref "XS1") (pin "2") (pinfunction "2_2") (pintype "passive"))
    )
    (net (code "60") (name "unconnected-(DA2-NC-Pad3)") (class "Default")
      (node (ref "DA2") (pin "3") (pinfunction "NC_3") (pintype "power_in"))
    )
    (net (code "61") (name "unconnected-(DD1-RA1{slash}AN1{slash}C2INA{slash}VBG{slash}CTDIN{slash}PMA7{slash}RP1-Pad20)") (class "Default")
      (node (ref "DD1") (pin "20") (pinfunction "RA1/AN1/C2INA/VBG/CTDIN/PMA7/RP1_20") (pintype "passive"))
    )
    (net (code "62") (name "unconnected-(DD1-RB0{slash}AN12{slash}C3IND{slash}INT0{slash}RP3-Pad8)") (class "Default")
      (node (ref "DD1") (pin "8") (pinfunction "RB0/AN12/C3IND/INT0/RP3_8") (pintype "passive"))
    )
    (net (code "63") (name "unconnected-(DD1-RB1{slash}AN10{slash}C3INC{slash}PMBE{slash}RTCC{slash}RP4-Pad9)") (class "Default")
      (node (ref "DD1") (pin "9") (pinfunction "RB1/AN10/C3INC/PMBE/RTCC/RP4_9") (pintype "passive"))
    )
    (net (code "64") (name "unconnected-(DD1-RB2{slash}AN8{slash}C2INC{slash}CTED1{slash}PMA3{slash}REFO{slash}RP5-Pad10)") (class "Default")
      (node (ref "DD1") (pin "10") (pinfunction "RB2/AN8/C2INC/CTED1/PMA3/REFO/RP5_10") (pintype "passive"))
    )
    (net (code "65") (name "unconnected-(DD1-RB5{slash}CCP5{slash}PMA0{slash}KBI1{slash}RP8-Pad15)") (class "Default")
      (node (ref "DD1") (pin "15") (pinfunction "RB5/CCP5/PMA0/KBI1/RP8_15") (pintype "passive"))
    )
    (net (code "66") (name "unconnected-(DD1-RB6{slash}CCP6{slash}KBI2{slash}PGC{slash}RP9-Pad16)") (class "Default")
      (node (ref "DD1") (pin "16") (pinfunction "RB6/CCP6/KBI2/PGC/RP9_16") (pintype "passive"))
    )
    (net (code "67") (name "unconnected-(DD1-RB7{slash}CCP7{slash}KBI3{slash}PGD{slash}RP10-Pad17)") (class "Default")
      (node (ref "DD1") (pin "17") (pinfunction "RB7/CCP7/KBI3/PGD/RP10_17") (pintype "passive"))
    )
    (net (code "68") (name "unconnected-(DD1-RC5{slash}SDO1{slash}RP16-Pad43)") (class "Default")
      (node (ref "DD1") (pin "43") (pinfunction "RC5/SDO1/RP16_43") (pintype "passive"))
    )
    (net (code "69") (name "unconnected-(DD1-RC6{slash}CCP9{slash}PMA5{slash}TX1{slash}CK1{slash}RP17-Pad44)") (class "Default")
      (node (ref "DD1") (pin "44") (pinfunction "RC6/CCP9/PMA5/TX1/CK1/RP17_44") (pintype "passive"))
    )
    (net (code "70") (name "unconnected-(DD1-RD0{slash}PMD0{slash}SCL2-Pad38)") (class "Default")
      (node (ref "DD1") (pin "38") (pinfunction "RD0/PMD0/SCL2_38") (pintype "passive"))
    )
    (net (code "71") (name "unconnected-(DD1-RD4{slash}PMD4{slash}RP21-Pad2)") (class "Default")
      (node (ref "DD1") (pin "2") (pinfunction "RD4/PMD4/RP21_2") (pintype "passive"))
    )
    (net (code "72") (name "unconnected-(DD1-RD5{slash}PMD5{slash}RP22-Pad3)") (class "Default")
      (node (ref "DD1") (pin "3") (pinfunction "RD5/PMD5/RP22_3") (pintype "passive"))
    )
    (net (code "73") (name "unconnected-(DD1-RD7{slash}PMD7{slash}RP24-Pad5)") (class "Default")
      (node (ref "DD1") (pin "5") (pinfunction "RD7/PMD7/RP24_5") (pintype "passive"))
    )
    (net (code "74") (name "unconnected-(DD1-RE0{slash}AN5{slash}PMRD-Pad25)") (class "Default")
      (node (ref "DD1") (pin "25") (pinfunction "RE0/AN5/PMRD_25") (pintype "passive"))
    )
    (net (code "75") (name "unconnected-(DD1-RE2{slash}AN7{slash}PMCS-Pad27)") (class "Default")
      (node (ref "DD1") (pin "27") (pinfunction "RE2/AN7/PMCS_27") (pintype "passive"))
    )
    (net (code "76") (name "unconnected-(R32-Pad1)") (class "Default")
      (node (ref "R32") (pin "1") (pinfunction "1_1") (pintype "passive"))
    )
    (net (code "77") (name "unconnected-(R32-Pad2)") (class "Default")
      (node (ref "R32") (pin "2") (pinfunction "2_2") (pintype "passive"))
    )
    (net (code "78") (name "unconnected-(R34-Pad1)") (class "Default")
      (node (ref "R34") (pin "1") (pinfunction "1_1") (pintype "passive"))
    )
  )
)
